# X-Track_Power.net
KiCad netlist of a schematic drawn in Altium Designer
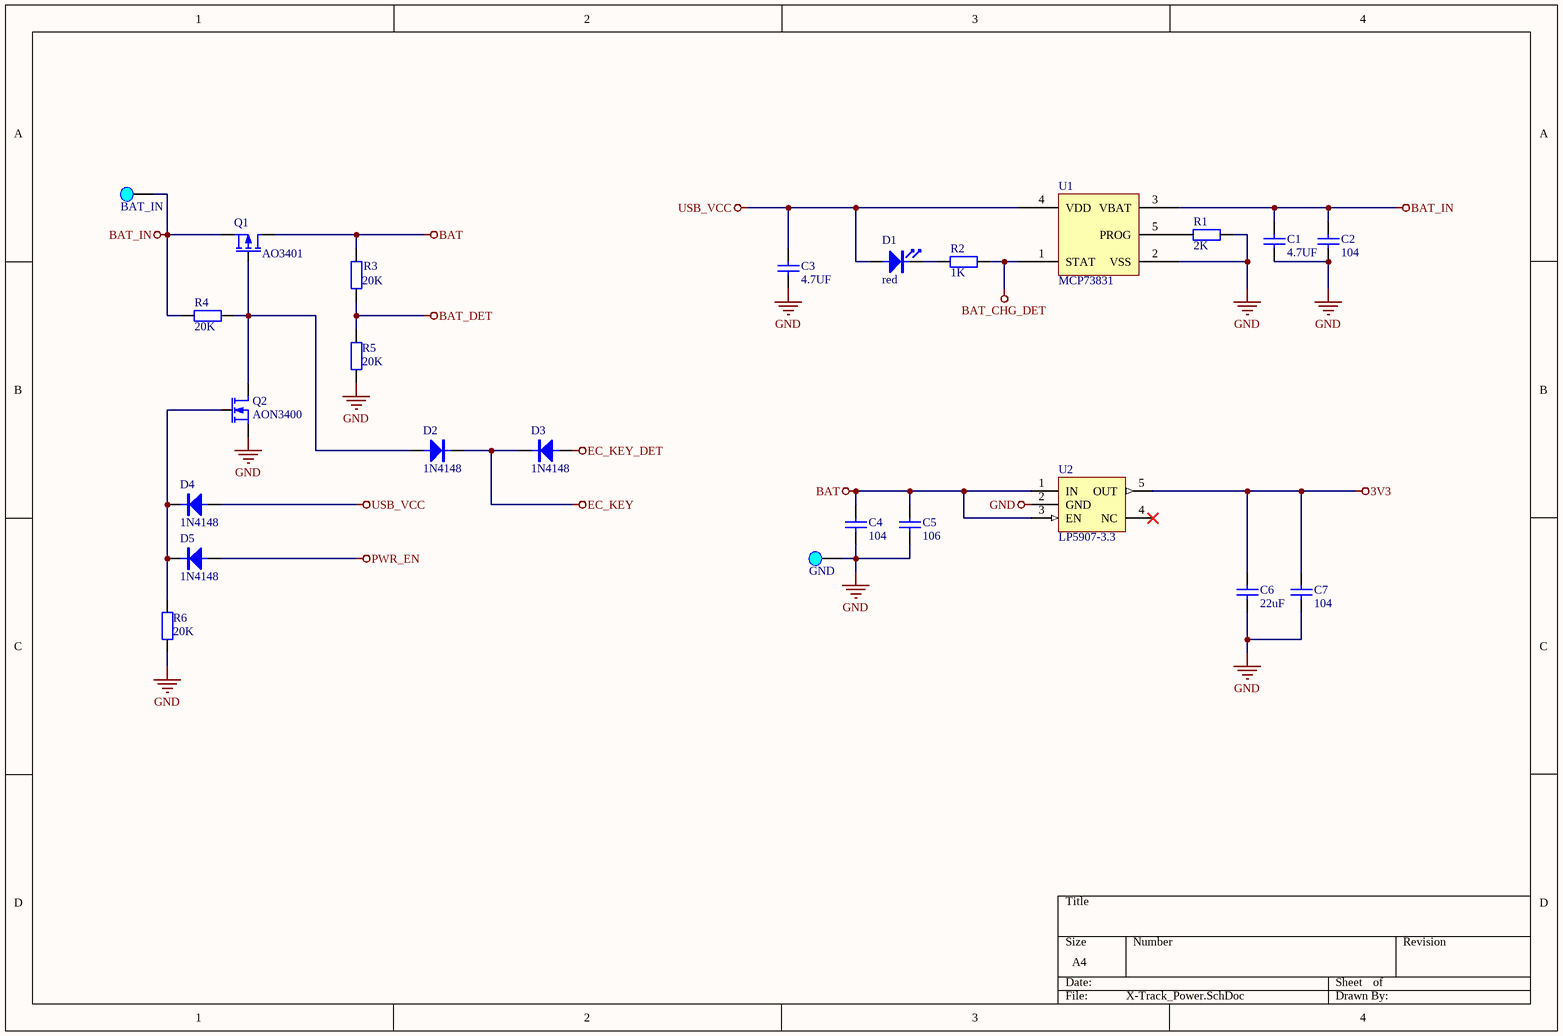
[diagram p0: X-Track_Power.SchDoc]

(export (version "E")
  (design (tool "Eeschema 10.0.6"))
  (components
    (comp (ref "BAT+")
      (value "BAT_IN")
      (footprint "Pad_B")
      (fields (field (name "_REMARKS") "BAT_IN"))
      (libsource (lib "元件库") (part "Pad"))
    )
    (comp (ref "BAT-")
      (value "GND")
      (footprint "Pad_B")
      (fields (field (name "_REMARKS") "GND"))
      (libsource (lib "元件库") (part "Pad"))
    )
    (comp (ref "C1")
      (value "4.7UF")
      (footprint "电容_C0805")
      (fields (field (name "C") "4.7UF"))
      (libsource (lib "元件库") (part "cap"))
    )
    (comp (ref "C2")
      (value "104")
      (footprint "电容_C0603")
      (fields (field (name "C") "104"))
      (libsource (lib "元件库") (part "cap"))
    )
    (comp (ref "C3")
      (value "4.7UF")
      (footprint "电容_C0805")
      (fields (field (name "C") "4.7UF"))
      (libsource (lib "元件库") (part "cap"))
    )
    (comp (ref "C4")
      (value "104")
      (footprint "电容_C0603")
      (fields (field (name "C") "104"))
      (libsource (lib "元件库") (part "cap"))
    )
    (comp (ref "C5")
      (value "106")
      (footprint "电容_C0603")
      (fields (field (name "C") "106"))
      (libsource (lib "元件库") (part "cap"))
    )
    (comp (ref "C6")
      (value "22uF")
      (footprint "电容_C1206")
      (fields (field (name "C") "22uF"))
      (libsource (lib "元件库") (part "cap"))
    )
    (comp (ref "C7")
      (value "104")
      (footprint "电容_C0603")
      (fields (field (name "C") "104"))
      (libsource (lib "元件库") (part "cap"))
    )
    (comp (ref "D1") (value "red") (footprint "LED_0603") (libsource (lib "元件库") (part "LED")))
    (comp (ref "D2")
      (value "1N4148")
      (footprint "二极管_SOD-323")
      (fields (field (name "_MODEL") "1N4148"))
      (libsource (lib "元件库") (part "Diode"))
    )
    (comp (ref "D3")
      (value "1N4148")
      (footprint "二极管_SOD-323")
      (fields (field (name "_MODEL") "1N4148"))
      (libsource (lib "元件库") (part "Diode"))
    )
    (comp (ref "D4")
      (value "1N4148")
      (footprint "二极管_SOD-323")
      (fields (field (name "_MODEL") "1N4148"))
      (libsource (lib "元件库") (part "Diode"))
    )
    (comp (ref "D5")
      (value "1N4148")
      (footprint "二极管_SOD-323")
      (fields (field (name "_MODEL") "1N4148"))
      (libsource (lib "元件库") (part "Diode"))
    )
    (comp (ref "Q1")
      (value "AO3401")
      (footprint "MOS_SOT-23")
      (fields (field (name "_MODEL") "AO3401"))
      (libsource (lib "元件库") (part "MOSFET-P"))
    )
    (comp (ref "Q2")
      (value "AON3400")
      (footprint "MOS_SOT-23")
      (fields (field (name "_MODEL") "AON3400"))
      (libsource (lib "元件库") (part "MOSFET-N"))
    )
    (comp (ref "R1")
      (value "2K")
      (footprint "电阻_R0603")
      (fields (field (name "R") "2K"))
      (libsource (lib "") (part "Res_2"))
    )
    (comp (ref "R2")
      (value "1K")
      (footprint "电阻_R0603")
      (fields (field (name "R") "1K"))
      (libsource (lib "") (part "Res_2"))
    )
    (comp (ref "R3")
      (value "20K")
      (footprint "电阻_R0603")
      (fields (field (name "R") "20K"))
      (libsource (lib "元件库") (part "Res"))
    )
    (comp (ref "R4")
      (value "20K")
      (footprint "电阻_R0603")
      (fields (field (name "R") "20K"))
      (libsource (lib "") (part "Res_3"))
    )
    (comp (ref "R5")
      (value "20K")
      (footprint "电阻_R0603")
      (fields (field (name "R") "20K"))
      (libsource (lib "元件库") (part "Res"))
    )
    (comp (ref "R6")
      (value "20K")
      (footprint "电阻_R0603")
      (fields (field (name "R") "20K"))
      (libsource (lib "") (part "Res_1"))
    )
    (comp (ref "U1")
      (value "MCP73831")
      (footprint "SOT23-5")
      (description "线性充电管理控制器")
      (libsource (lib "TriggersLib") (part "MCP73831"))
    )
    (comp (ref "U2")
      (value "LP5907-3.3")
      (footprint "SOT23-5")
      (description "LDO")
      (libsource (lib "WatchX_TEST") (part "LP5907"))
    )
  )
  (nets
    (net (code "1") (name "3V3") (class "Default")
      (node (ref "C6") (pin "2") (pinfunction "2_2") (pintype "passive"))
      (node (ref "C7") (pin "2") (pinfunction "2_2") (pintype "passive"))
      (node (ref "U2") (pin "5") (pinfunction "OUT_5") (pintype "output"))
    )
    (net (code "2") (name "BAT") (class "Default")
      (node (ref "C4") (pin "2") (pinfunction "2_2") (pintype "passive"))
      (node (ref "C5") (pin "2") (pinfunction "2_2") (pintype "passive"))
      (node (ref "Q1") (pin "2") (pinfunction "D_2") (pintype "passive"))
      (node (ref "R3") (pin "2") (pinfunction "2_2") (pintype "passive"))
      (node (ref "U2") (pin "1") (pinfunction "IN_1") (pintype "power_in"))
      (node (ref "U2") (pin "3") (pinfunction "EN_3") (pintype "input"))
    )
    (net (code "3") (name "BAT_CHG_DET") (class "Default")
      (node (ref "R2") (pin "1") (pinfunction "1_1") (pintype "passive"))
      (node (ref "U1") (pin "1") (pinfunction "STAT_1") (pintype "passive"))
    )
    (net (code "4") (name "BAT_DET") (class "Default")
      (node (ref "R3") (pin "1") (pinfunction "1_1") (pintype "passive"))
      (node (ref "R5") (pin "2") (pinfunction "2_2") (pintype "passive"))
    )
    (net (code "5") (name "BAT_IN") (class "Default")
      (node (ref "BAT+") (pin "1") (pinfunction "*_1") (pintype "passive"))
      (node (ref "C1") (pin "2") (pinfunction "2_2") (pintype "passive"))
      (node (ref "C2") (pin "1") (pinfunction "1_1") (pintype "passive"))
      (node (ref "Q1") (pin "3") (pinfunction "S_3") (pintype "passive"))
      (node (ref "R4") (pin "1") (pinfunction "1_1") (pintype "passive"))
      (node (ref "U1") (pin "3") (pinfunction "VBAT_3") (pintype "passive"))
    )
    (net (code "6") (name "EC_KEY") (class "Default")
      (node (ref "D2") (pin "K") (pinfunction "K_K") (pintype "passive"))
      (node (ref "D3") (pin "K") (pinfunction "K_K") (pintype "passive"))
    )
    (net (code "7") (name "EC_KEY_DET") (class "Default")
      (node (ref "D3") (pin "A") (pinfunction "A_A") (pintype "passive"))
    )
    (net (code "8") (name "GND") (class "Default")
      (node (ref "BAT-") (pin "1") (pinfunction "*_1") (pintype "passive"))
      (node (ref "C1") (pin "1") (pinfunction "1_1") (pintype "passive"))
      (node (ref "C2") (pin "2") (pinfunction "2_2") (pintype "passive"))
      (node (ref "C3") (pin "1") (pinfunction "1_1") (pintype "passive"))
      (node (ref "C4") (pin "1") (pinfunction "1_1") (pintype "passive"))
      (node (ref "C5") (pin "1") (pinfunction "1_1") (pintype "passive"))
      (node (ref "C6") (pin "1") (pinfunction "1_1") (pintype "passive"))
      (node (ref "C7") (pin "1") (pinfunction "1_1") (pintype "passive"))
      (node (ref "Q2") (pin "3") (pinfunction "S_3") (pintype "passive"))
      (node (ref "R1") (pin "1") (pinfunction "1_1") (pintype "passive"))
      (node (ref "R5") (pin "1") (pinfunction "1_1") (pintype "passive"))
      (node (ref "R6") (pin "2") (pinfunction "2_2") (pintype "passive"))
      (node (ref "U1") (pin "2") (pinfunction "VSS_2") (pintype "passive"))
      (node (ref "U2") (pin "2") (pinfunction "GND_2") (pintype "passive"))
    )
    (net (code "9") (name "Net-(D1-PadK)") (class "Default")
      (node (ref "D1") (pin "K") (pinfunction "K_K") (pintype "passive"))
      (node (ref "R2") (pin "2") (pinfunction "2_2") (pintype "passive"))
    )
    (net (code "10") (name "Net-(Q1-G)") (class "Default")
      (node (ref "D2") (pin "A") (pinfunction "A_A") (pintype "passive"))
      (node (ref "Q1") (pin "1") (pinfunction "G_1") (pintype "passive"))
      (node (ref "Q2") (pin "2") (pinfunction "D_2") (pintype "passive"))
      (node (ref "R4") (pin "2") (pinfunction "2_2") (pintype "passive"))
    )
    (net (code "11") (name "Net-(Q2-G)") (class "Default")
      (node (ref "D4") (pin "K") (pinfunction "K_K") (pintype "passive"))
      (node (ref "D5") (pin "K") (pinfunction "K_K") (pintype "passive"))
      (node (ref "Q2") (pin "1") (pinfunction "G_1") (pintype "passive"))
      (node (ref "R6") (pin "1") (pinfunction "1_1") (pintype "passive"))
    )
    (net (code "12") (name "Net-(U1-PROG)") (class "Default")
      (node (ref "R1") (pin "2") (pinfunction "2_2") (pintype "passive"))
      (node (ref "U1") (pin "5") (pinfunction "PROG_5") (pintype "passive"))
    )
    (net (code "13") (name "PWR_EN") (class "Default")
      (node (ref "D5") (pin "A") (pinfunction "A_A") (pintype "passive"))
    )
    (net (code "14") (name "USB_VCC") (class "Default")
      (node (ref "C3") (pin "2") (pinfunction "2_2") (pintype "passive"))
      (node (ref "D1") (pin "A") (pinfunction "A_A") (pintype "passive"))
      (node (ref "D4") (pin "A") (pinfunction "A_A") (pintype "passive"))
      (node (ref "U1") (pin "4") (pinfunction "VDD_4") (pintype "passive"))
    )
    (net (code "15") (name "unconnected-(U2-NC-Pad4)") (class "Default")
      (node (ref "U2") (pin "4") (pinfunction "NC_4") (pintype "passive+no_connect"))
    )
  )
)
